# ring-modulator-v3_0.net
KiCad netlist of a schematic drawn in EAGLE
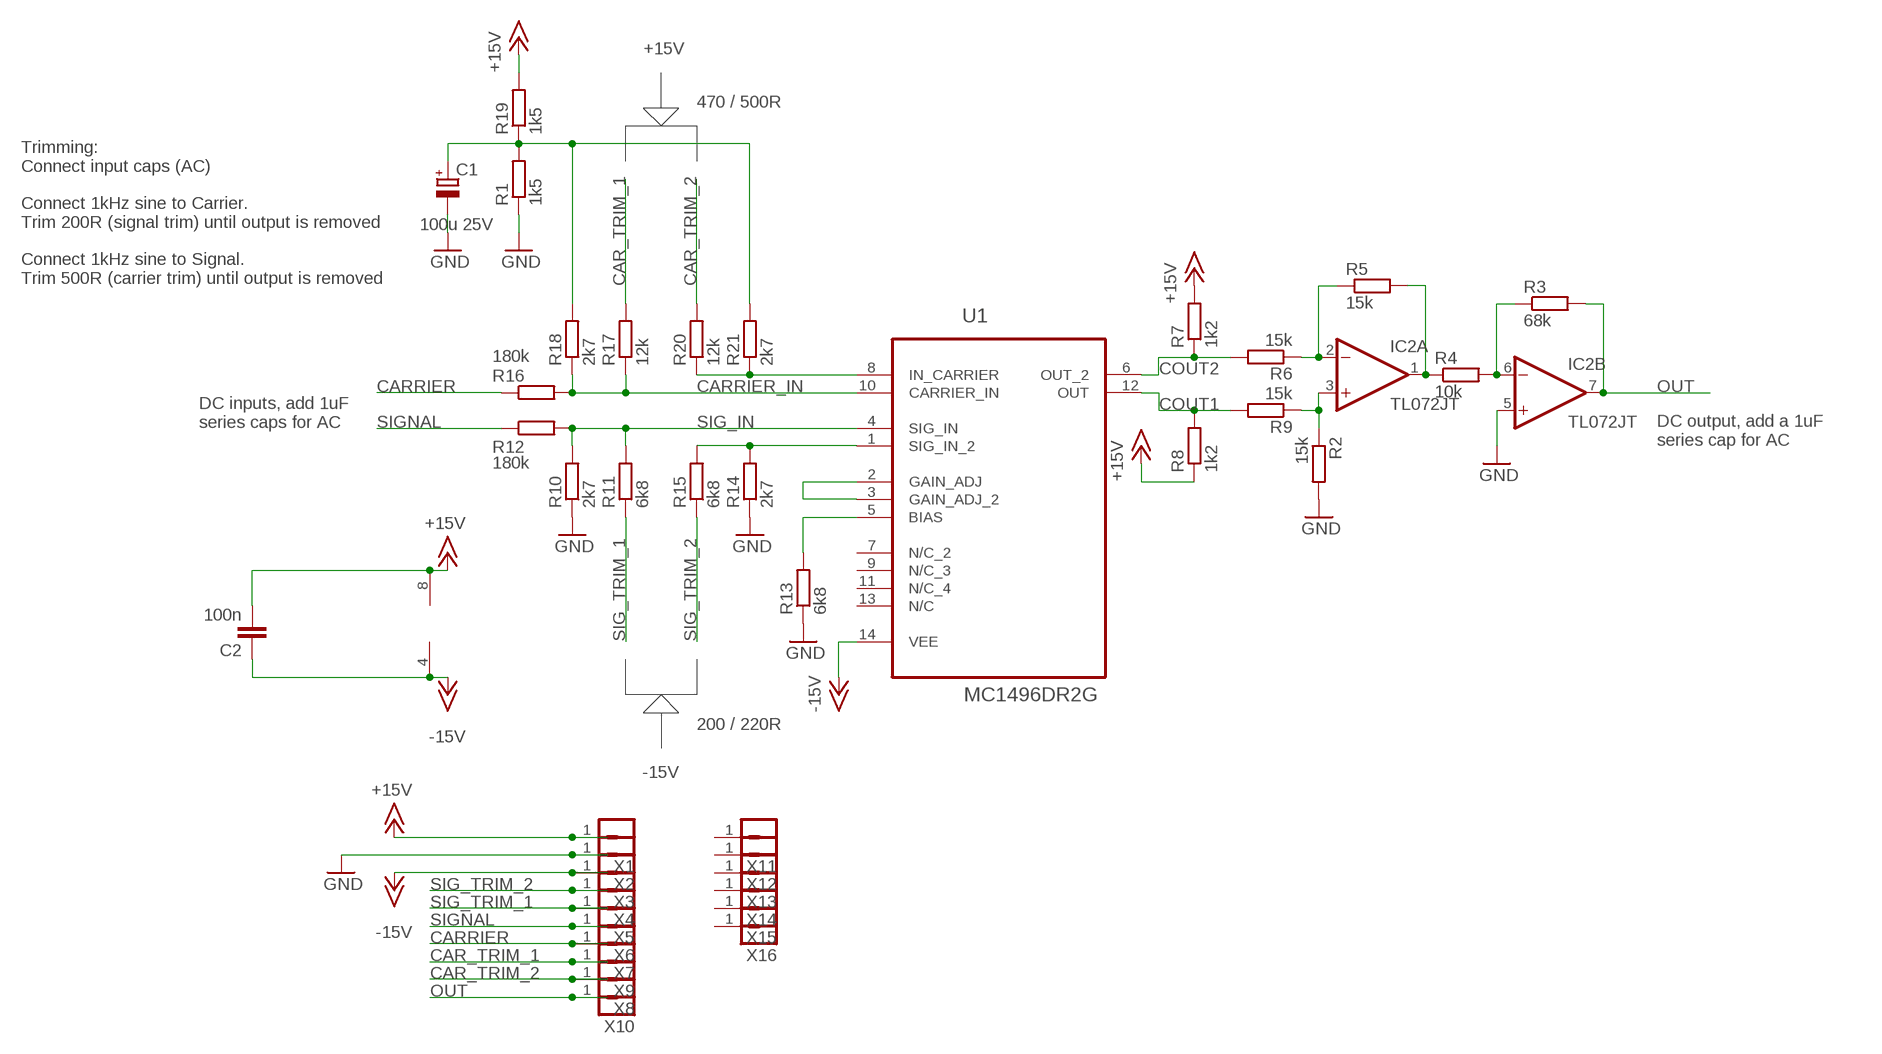
[diagram p0: schematic, sheet 1]

(export (version "E")
  (design (tool "Eeschema 10.0.6"))
  (components
    (comp (ref "C1")
      (value "100u 25V")
      (footprint "eagle-import:UD-4X5,8_NICHICON")
      (libsource (lib "eagle-import") (part "CPOL-EUUD-4X5,8"))
    )
    (comp (ref "C2")
      (value "100n")
      (footprint "eagle-import:C0603")
      (libsource (lib "eagle-import") (part "C-EUC0603"))
    )
    (comp (ref "IC2")
      (value "TL072JT")
      (footprint "eagle-import:TSSOP8J")
      (libsource (lib "eagle-import") (part "TL072JT"))
    )
    (comp (ref "R1")
      (value "1k5")
      (footprint "eagle-import:R0402")
      (libsource (lib "eagle-import") (part "R-EU_R0402"))
    )
    (comp (ref "R2")
      (value "15k")
      (footprint "eagle-import:R0402")
      (libsource (lib "eagle-import") (part "R-EU_R0402"))
    )
    (comp (ref "R3")
      (value "68k")
      (footprint "eagle-import:R0402")
      (libsource (lib "eagle-import") (part "R-EU_R0402"))
    )
    (comp (ref "R4")
      (value "10k")
      (footprint "eagle-import:R0402")
      (libsource (lib "eagle-import") (part "R-EU_R0402"))
    )
    (comp (ref "R5")
      (value "15k")
      (footprint "eagle-import:R0402")
      (libsource (lib "eagle-import") (part "R-EU_R0402"))
    )
    (comp (ref "R6")
      (value "15k")
      (footprint "eagle-import:R0402")
      (libsource (lib "eagle-import") (part "R-EU_R0402"))
    )
    (comp (ref "R7")
      (value "1k2")
      (footprint "eagle-import:R0402")
      (libsource (lib "eagle-import") (part "R-EU_R0402"))
    )
    (comp (ref "R8")
      (value "1k2")
      (footprint "eagle-import:R0402")
      (libsource (lib "eagle-import") (part "R-EU_R0402"))
    )
    (comp (ref "R9")
      (value "15k")
      (footprint "eagle-import:R0402")
      (libsource (lib "eagle-import") (part "R-EU_R0402"))
    )
    (comp (ref "R10")
      (value "2k7")
      (footprint "eagle-import:R0402")
      (libsource (lib "eagle-import") (part "R-EU_R0402"))
    )
    (comp (ref "R11")
      (value "6k8")
      (footprint "eagle-import:R0402")
      (libsource (lib "eagle-import") (part "R-EU_R0402"))
    )
    (comp (ref "R12")
      (value "180k")
      (footprint "eagle-import:R0402")
      (libsource (lib "eagle-import") (part "R-EU_R0402"))
    )
    (comp (ref "R13")
      (value "6k8")
      (footprint "eagle-import:R0402")
      (libsource (lib "eagle-import") (part "R-EU_R0402"))
    )
    (comp (ref "R14")
      (value "2k7")
      (footprint "eagle-import:R0402")
      (libsource (lib "eagle-import") (part "R-EU_R0402"))
    )
    (comp (ref "R15")
      (value "6k8")
      (footprint "eagle-import:R0402")
      (libsource (lib "eagle-import") (part "R-EU_R0402"))
    )
    (comp (ref "R16")
      (value "180k")
      (footprint "eagle-import:R0402")
      (libsource (lib "eagle-import") (part "R-EU_R0402"))
    )
    (comp (ref "R17")
      (value "12k")
      (footprint "eagle-import:R0402")
      (libsource (lib "eagle-import") (part "R-EU_R0402"))
    )
    (comp (ref "R18")
      (value "2k7")
      (footprint "eagle-import:R0402")
      (libsource (lib "eagle-import") (part "R-EU_R0402"))
    )
    (comp (ref "R19")
      (value "1k5")
      (footprint "eagle-import:R0402")
      (libsource (lib "eagle-import") (part "R-EU_R0402"))
    )
    (comp (ref "R20")
      (value "12k")
      (footprint "eagle-import:R0402")
      (libsource (lib "eagle-import") (part "R-EU_R0402"))
    )
    (comp (ref "R21")
      (value "2k7")
      (footprint "eagle-import:R0402")
      (libsource (lib "eagle-import") (part "R-EU_R0402"))
    )
    (comp (ref "U1")
      (value "MC1496DR2G")
      (footprint "eagle-import:SOIC127P600X175-14N")
      (libsource (lib "eagle-import") (part "MC1496DR2G"))
    )
    (comp (ref "X1")
      (value "MA01-1JN")
      (footprint "eagle-import:MA01N-1J")
      (libsource (lib "eagle-import") (part "MA01-1JN"))
    )
    (comp (ref "X2")
      (value "MA01-1JN")
      (footprint "eagle-import:MA01N-1J")
      (libsource (lib "eagle-import") (part "MA01-1JN"))
    )
    (comp (ref "X3")
      (value "MA01-1JN")
      (footprint "eagle-import:MA01N-1J")
      (libsource (lib "eagle-import") (part "MA01-1JN"))
    )
    (comp (ref "X4")
      (value "MA01-1JN")
      (footprint "eagle-import:MA01N-1J")
      (libsource (lib "eagle-import") (part "MA01-1JN"))
    )
    (comp (ref "X5")
      (value "MA01-1JN")
      (footprint "eagle-import:MA01N-1J")
      (libsource (lib "eagle-import") (part "MA01-1JN"))
    )
    (comp (ref "X6")
      (value "MA01-1JN")
      (footprint "eagle-import:MA01N-1J")
      (libsource (lib "eagle-import") (part "MA01-1JN"))
    )
    (comp (ref "X7")
      (value "MA01-1JN")
      (footprint "eagle-import:MA01N-1J")
      (libsource (lib "eagle-import") (part "MA01-1JN"))
    )
    (comp (ref "X8")
      (value "MA01-1JN")
      (footprint "eagle-import:MA01N-1J")
      (libsource (lib "eagle-import") (part "MA01-1JN"))
    )
    (comp (ref "X9")
      (value "MA01-1JN")
      (footprint "eagle-import:MA01N-1J")
      (libsource (lib "eagle-import") (part "MA01-1JN"))
    )
    (comp (ref "X10")
      (value "MA01-1JN")
      (footprint "eagle-import:MA01N-1J")
      (libsource (lib "eagle-import") (part "MA01-1JN"))
    )
    (comp (ref "X11")
      (value "MA01-1JN")
      (footprint "eagle-import:MA01N-1J")
      (libsource (lib "eagle-import") (part "MA01-1JN"))
    )
    (comp (ref "X12")
      (value "MA01-1JN")
      (footprint "eagle-import:MA01N-1J")
      (libsource (lib "eagle-import") (part "MA01-1JN"))
    )
    (comp (ref "X13")
      (value "MA01-1JN")
      (footprint "eagle-import:MA01N-1J")
      (libsource (lib "eagle-import") (part "MA01-1JN"))
    )
    (comp (ref "X14")
      (value "MA01-1JN")
      (footprint "eagle-import:MA01N-1J")
      (libsource (lib "eagle-import") (part "MA01-1JN"))
    )
    (comp (ref "X15")
      (value "MA01-1JN")
      (footprint "eagle-import:MA01N-1J")
      (libsource (lib "eagle-import") (part "MA01-1JN"))
    )
    (comp (ref "X16")
      (value "MA01-1JN")
      (footprint "eagle-import:MA01N-1J")
      (libsource (lib "eagle-import") (part "MA01-1JN"))
    )
  )
  (nets
    (net (code "1") (name "+15V") (class "Default")
      (node (ref "C2") (pin "2") (pinfunction "2_2") (pintype "passive"))
      (node (ref "IC2") (pin "8") (pinfunction "V+_8") (pintype "power_in"))
      (node (ref "R19") (pin "2") (pinfunction "2_2") (pintype "passive"))
      (node (ref "R7") (pin "2") (pinfunction "2_2") (pintype "passive"))
      (node (ref "R8") (pin "1") (pinfunction "1_1") (pintype "passive"))
      (node (ref "X1") (pin "1") (pinfunction "1_1") (pintype "passive"))
    )
    (net (code "2") (name "-15V") (class "Default")
      (node (ref "C2") (pin "1") (pinfunction "1_1") (pintype "passive"))
      (node (ref "IC2") (pin "4") (pinfunction "V-_4") (pintype "power_in"))
      (node (ref "U1") (pin "14") (pinfunction "VEE_14") (pintype "passive"))
      (node (ref "X3") (pin "1") (pinfunction "1_1") (pintype "passive"))
    )
    (net (code "3") (name "/CARRIER") (class "Default")
      (node (ref "R16") (pin "1") (pinfunction "1_1") (pintype "passive"))
      (node (ref "X7") (pin "1") (pinfunction "1_1") (pintype "passive"))
    )
    (net (code "4") (name "/CARRIER_IN") (class "Default")
      (node (ref "R16") (pin "2") (pinfunction "2_2") (pintype "passive"))
      (node (ref "R17") (pin "1") (pinfunction "1_1") (pintype "passive"))
      (node (ref "R18") (pin "1") (pinfunction "1_1") (pintype "passive"))
      (node (ref "U1") (pin "10") (pinfunction "CARRIER_IN_10") (pintype "power_in"))
    )
    (net (code "5") (name "/CAR_TRIM_1") (class "Default")
      (node (ref "R17") (pin "2") (pinfunction "2_2") (pintype "passive"))
      (node (ref "X9") (pin "1") (pinfunction "1_1") (pintype "passive"))
    )
    (net (code "6") (name "/CAR_TRIM_2") (class "Default")
      (node (ref "R20") (pin "2") (pinfunction "2_2") (pintype "passive"))
      (node (ref "X8") (pin "1") (pinfunction "1_1") (pintype "passive"))
    )
    (net (code "7") (name "/COUT1") (class "Default")
      (node (ref "R8") (pin "2") (pinfunction "2_2") (pintype "passive"))
      (node (ref "R9") (pin "2") (pinfunction "2_2") (pintype "passive"))
      (node (ref "U1") (pin "12") (pinfunction "OUT_12") (pintype "output"))
    )
    (net (code "8") (name "/COUT2") (class "Default")
      (node (ref "R6") (pin "2") (pinfunction "2_2") (pintype "passive"))
      (node (ref "R7") (pin "1") (pinfunction "1_1") (pintype "passive"))
      (node (ref "U1") (pin "6") (pinfunction "OUT_2_6") (pintype "output"))
    )
    (net (code "9") (name "/OUT") (class "Default")
      (node (ref "IC2") (pin "7") (pinfunction "OUT_7") (pintype "output"))
      (node (ref "R3") (pin "2") (pinfunction "2_2") (pintype "passive"))
      (node (ref "X10") (pin "1") (pinfunction "1_1") (pintype "passive"))
    )
    (net (code "10") (name "/SIGNAL") (class "Default")
      (node (ref "R12") (pin "1") (pinfunction "1_1") (pintype "passive"))
      (node (ref "X6") (pin "1") (pinfunction "1_1") (pintype "passive"))
    )
    (net (code "11") (name "/SIG_IN") (class "Default")
      (node (ref "R10") (pin "2") (pinfunction "2_2") (pintype "passive"))
      (node (ref "R11") (pin "2") (pinfunction "2_2") (pintype "passive"))
      (node (ref "R12") (pin "2") (pinfunction "2_2") (pintype "passive"))
      (node (ref "U1") (pin "4") (pinfunction "SIG_IN_4") (pintype "input"))
    )
    (net (code "12") (name "/SIG_TRIM_1") (class "Default")
      (node (ref "R11") (pin "1") (pinfunction "1_1") (pintype "passive"))
      (node (ref "X5") (pin "1") (pinfunction "1_1") (pintype "passive"))
    )
    (net (code "13") (name "/SIG_TRIM_2") (class "Default")
      (node (ref "R15") (pin "1") (pinfunction "1_1") (pintype "passive"))
      (node (ref "X4") (pin "1") (pinfunction "1_1") (pintype "passive"))
    )
    (net (code "14") (name "GND") (class "Default")
      (node (ref "C1") (pin "-") (pinfunction "-_-") (pintype "passive"))
      (node (ref "IC2") (pin "5") (pinfunction "+IN_5") (pintype "input"))
      (node (ref "R1") (pin "1") (pinfunction "1_1") (pintype "passive"))
      (node (ref "R10") (pin "1") (pinfunction "1_1") (pintype "passive"))
      (node (ref "R13") (pin "1") (pinfunction "1_1") (pintype "passive"))
      (node (ref "R14") (pin "1") (pinfunction "1_1") (pintype "passive"))
      (node (ref "R2") (pin "2") (pinfunction "2_2") (pintype "passive"))
      (node (ref "X2") (pin "1") (pinfunction "1_1") (pintype "passive"))
    )
    (net (code "15") (name "Net-(C1-Pad+)") (class "Default")
      (node (ref "C1") (pin "+") (pinfunction "+_+") (pintype "passive"))
      (node (ref "R1") (pin "2") (pinfunction "2_2") (pintype "passive"))
      (node (ref "R18") (pin "2") (pinfunction "2_2") (pintype "passive"))
      (node (ref "R19") (pin "1") (pinfunction "1_1") (pintype "passive"))
      (node (ref "R21") (pin "2") (pinfunction "2_2") (pintype "passive"))
    )
    (net (code "16") (name "Net-(IC2A-+IN)") (class "Default")
      (node (ref "IC2") (pin "3") (pinfunction "+IN_3") (pintype "input"))
      (node (ref "R2") (pin "1") (pinfunction "1_1") (pintype "passive"))
      (node (ref "R9") (pin "1") (pinfunction "1_1") (pintype "passive"))
    )
    (net (code "17") (name "Net-(IC2A--IN)") (class "Default")
      (node (ref "IC2") (pin "2") (pinfunction "-IN_2") (pintype "input"))
      (node (ref "R5") (pin "1") (pinfunction "1_1") (pintype "passive"))
      (node (ref "R6") (pin "1") (pinfunction "1_1") (pintype "passive"))
    )
    (net (code "18") (name "Net-(IC2A-OUT)") (class "Default")
      (node (ref "IC2") (pin "1") (pinfunction "OUT_1") (pintype "output"))
      (node (ref "R4") (pin "1") (pinfunction "1_1") (pintype "passive"))
      (node (ref "R5") (pin "2") (pinfunction "2_2") (pintype "passive"))
    )
    (net (code "19") (name "Net-(IC2B--IN)") (class "Default")
      (node (ref "IC2") (pin "6") (pinfunction "-IN_6") (pintype "input"))
      (node (ref "R3") (pin "1") (pinfunction "1_1") (pintype "passive"))
      (node (ref "R4") (pin "2") (pinfunction "2_2") (pintype "passive"))
    )
    (net (code "20") (name "Net-(U1-BIAS)") (class "Default")
      (node (ref "R13") (pin "2") (pinfunction "2_2") (pintype "passive"))
      (node (ref "U1") (pin "5") (pinfunction "BIAS_5") (pintype "input"))
    )
    (net (code "21") (name "Net-(U1-GAIN_ADJ)") (class "Default")
      (node (ref "U1") (pin "2") (pinfunction "GAIN_ADJ_2") (pintype "input"))
      (node (ref "U1") (pin "3") (pinfunction "GAIN_ADJ_2_3") (pintype "input"))
    )
    (net (code "22") (name "Net-(U1-IN_CARRIER)") (class "Default")
      (node (ref "R20") (pin "1") (pinfunction "1_1") (pintype "passive"))
      (node (ref "R21") (pin "1") (pinfunction "1_1") (pintype "passive"))
      (node (ref "U1") (pin "8") (pinfunction "IN_CARRIER_8") (pintype "power_in"))
    )
    (net (code "23") (name "Net-(U1-SIG_IN_2)") (class "Default")
      (node (ref "R14") (pin "2") (pinfunction "2_2") (pintype "passive"))
      (node (ref "R15") (pin "2") (pinfunction "2_2") (pintype "passive"))
      (node (ref "U1") (pin "1") (pinfunction "SIG_IN_2_1") (pintype "input"))
    )
    (net (code "24") (name "unconnected-(U1-N{slash}C-Pad13)") (class "Default")
      (node (ref "U1") (pin "13") (pinfunction "N/C_13") (pintype "no_connect"))
    )
    (net (code "25") (name "unconnected-(U1-N{slash}C_2-Pad7)") (class "Default")
      (node (ref "U1") (pin "7") (pinfunction "N/C_2_7") (pintype "no_connect"))
    )
    (net (code "26") (name "unconnected-(U1-N{slash}C_3-Pad9)") (class "Default")
      (node (ref "U1") (pin "9") (pinfunction "N/C_3_9") (pintype "no_connect"))
    )
    (net (code "27") (name "unconnected-(U1-N{slash}C_4-Pad11)") (class "Default")
      (node (ref "U1") (pin "11") (pinfunction "N/C_4_11") (pintype "no_connect"))
    )
    (net (code "28") (name "unconnected-(X11-Pad1)") (class "Default")
      (node (ref "X11") (pin "1") (pinfunction "1_1") (pintype "passive"))
    )
    (net (code "29") (name "unconnected-(X12-Pad1)") (class "Default")
      (node (ref "X12") (pin "1") (pinfunction "1_1") (pintype "passive"))
    )
    (net (code "30") (name "unconnected-(X13-Pad1)") (class "Default")
      (node (ref "X13") (pin "1") (pinfunction "1_1") (pintype "passive"))
    )
    (net (code "31") (name "unconnected-(X14-Pad1)") (class "Default")
      (node (ref "X14") (pin "1") (pinfunction "1_1") (pintype "passive"))
    )
    (net (code "32") (name "unconnected-(X15-Pad1)") (class "Default")
      (node (ref "X15") (pin "1") (pinfunction "1_1") (pintype "passive"))
    )
    (net (code "33") (name "unconnected-(X16-Pad1)") (class "Default")
      (node (ref "X16") (pin "1") (pinfunction "1_1") (pintype "passive"))
    )
  )
)
